# LP_ECG_Power-X02.net
KiCad netlist of a schematic drawn in Altium Designer
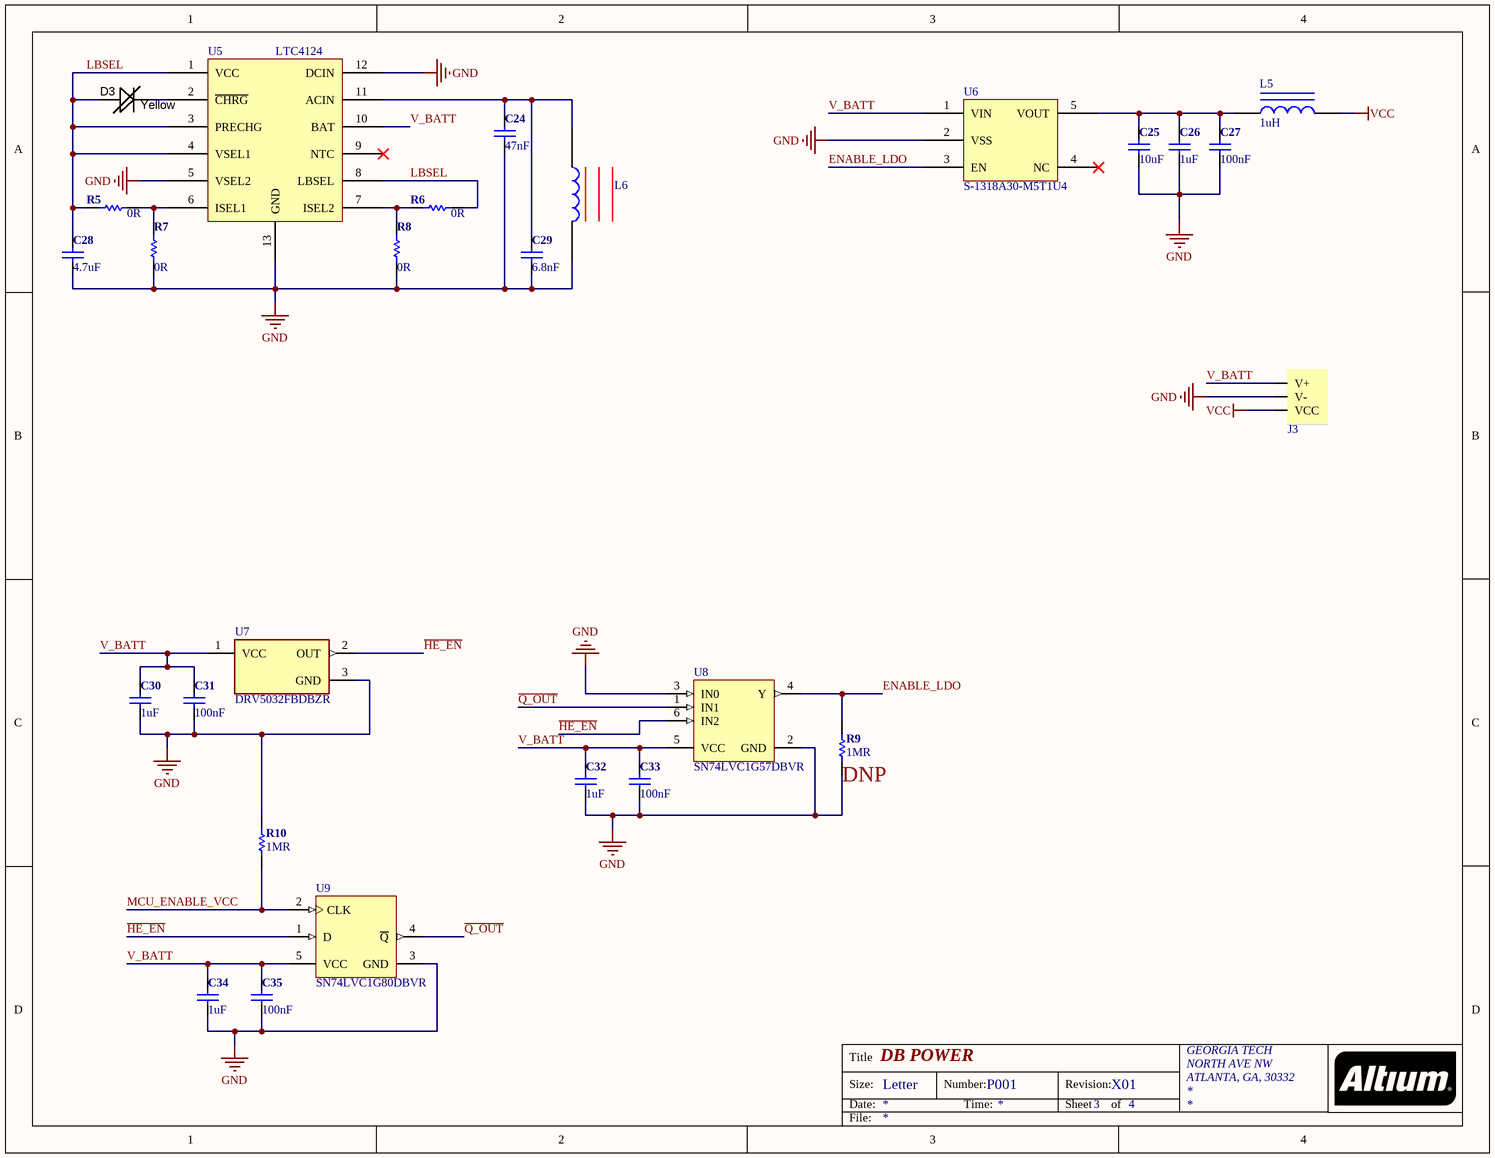
[diagram p0: LP_ECG_Power-X02.SchDoc]

(export (version "E")
  (design (tool "Eeschema 10.0.6"))
  (components
    (comp (ref "C24")
      (value "47nF")
      (footprint "C0402")
      (fields
        (field (name "MANUFACTURER") "Murata")
        (field (name "MANUFACTURER PART NUMBER") "GCM155R71H473KE02D")
      )
      (libsource (lib "LP_ECG-X02") (part "C-0402(1005)"))
    )
    (comp (ref "C25")
      (value "10uF")
      (footprint "C0402")
      (fields
        (field (name "MANUFACTURER") "Kyocera AVX")
        (field (name "MANUFACTURER PART NUMBER") "0402ZD106MAT2A")
      )
      (libsource (lib "LP_ECG-X01") (part "C-0402(1005)"))
    )
    (comp (ref "C26")
      (value "1uF")
      (footprint "C0402")
      (fields
        (field (name "MANUFACTURER") "Yageo")
        (field (name "MANUFACTURER PART NUMBER") "CC0402MRX5R5BB105")
        (field (name "TOLERANCE") "20%")
      )
      (libsource (lib "LP_ECG-X01") (part "C-0402(1005)"))
    )
    (comp (ref "C27")
      (value "100nF")
      (footprint "C0402")
      (fields
        (field (name "MANUFACTURER") "Taiyo Yuden")
        (field (name "MANUFACTURER PART NUMBER") "TMK105BJ104KV-F")
        (field (name "TOLERANCE") "10%")
      )
      (libsource (lib "LP_ECG-X01") (part "C-0402(1005)"))
    )
    (comp (ref "C28")
      (value "4.7uF")
      (footprint "C0402")
      (fields
        (field (name "MANUFACTURER") "Murata")
        (field (name "MANUFACTURER PART NUMBER") "GRM155R60J475ME87J")
      )
      (libsource (lib "LP_ECG-X02") (part "C-0402(1005)"))
    )
    (comp (ref "C29")
      (value "6.8nF")
      (footprint "C0402")
      (fields
        (field (name "MANUFACTURER") "Murata")
        (field (name "MANUFACTURER PART NUMBER") "GCM155R71H682KA55D")
      )
      (libsource (lib "LP_ECG-X02") (part "C-0402(1005)"))
    )
    (comp (ref "C30")
      (value "1uF")
      (footprint "C0402")
      (fields
        (field (name "MANUFACTURER") "Yageo")
        (field (name "MANUFACTURER PART NUMBER") "CC0402MRX5R5BB105")
        (field (name "TOLERANCE") "20%")
      )
      (libsource (lib "LP_ECG-X01") (part "C-0402(1005)"))
    )
    (comp (ref "C31")
      (value "100nF")
      (footprint "C0402")
      (fields
        (field (name "MANUFACTURER") "Taiyo Yuden")
        (field (name "MANUFACTURER PART NUMBER") "TMK105BJ104KV-F")
        (field (name "TOLERANCE") "10%")
      )
      (libsource (lib "LP_ECG-X01") (part "C-0402(1005)"))
    )
    (comp (ref "C32")
      (value "1uF")
      (footprint "C0402")
      (fields
        (field (name "MANUFACTURER") "Yageo")
        (field (name "MANUFACTURER PART NUMBER") "CC0402MRX5R5BB105")
        (field (name "TOLERANCE") "20%")
      )
      (libsource (lib "LP_ECG-X01") (part "C-0402(1005)"))
    )
    (comp (ref "C33")
      (value "100nF")
      (footprint "C0402")
      (fields
        (field (name "MANUFACTURER") "Taiyo Yuden")
        (field (name "MANUFACTURER PART NUMBER") "TMK105BJ104KV-F")
        (field (name "TOLERANCE") "10%")
      )
      (libsource (lib "LP_ECG-X01") (part "C-0402(1005)"))
    )
    (comp (ref "C34")
      (value "1uF")
      (footprint "C0402")
      (fields
        (field (name "MANUFACTURER") "Yageo")
        (field (name "MANUFACTURER PART NUMBER") "CC0402MRX5R5BB105")
        (field (name "TOLERANCE") "20%")
      )
      (libsource (lib "LP_ECG-X01") (part "C-0402(1005)"))
    )
    (comp (ref "C35")
      (value "100nF")
      (footprint "C0402")
      (fields
        (field (name "MANUFACTURER") "Taiyo Yuden")
        (field (name "MANUFACTURER PART NUMBER") "TMK105BJ104KV-F")
        (field (name "TOLERANCE") "10%")
      )
      (libsource (lib "LP_ECG-X01") (part "C-0402(1005)"))
    )
    (comp (ref "D3")
      (value "Yellow")
      (footprint "LED_0402")
      (description "Single Color LED, Super Bright Yellow, Water Clear, 0.8mm")
      (fields
        (field (name "MANUFACTURER") "Kingbright")
        (field (name "MANUFACTURER PART NUMBER") "APHHS1005SYCK")
      )
      (libsource (lib "LP_ECG-X01") (part "LED_0402(1005)"))
    )
    (comp (ref "J3")
      (value "SMD CONNECTOR FOR 40 mAh BATTERY")
      (footprint "battery_connector")
      (description "Lithium Battery 3.7V 40mAh Rechargeable")
      (libsource (lib "LP_ECG-X01") (part "SMD_BATTERY_CONNECTOR"))
    )
    (comp (ref "L5")
      (value "1uH")
      (footprint "L0402")
      (description "General Purpose Inductor, 1uH, 20%, 1 Element, Ferrite-Core, SMD, 0402")
      (fields
        (field (name "MANUFACTURER") "TDK")
        (field (name "MANUFACTURER PART NUMBER") "MLZ1005M1R0WT000")
      )
      (libsource (lib "LP_ECG-X01") (part "Inductor Iron"))
    )
    (comp (ref "L6")
      (value "WIRELESS CHARGING COIL, RECEIVER")
      (footprint "760308101219")
      (description "General Purpose Inductor, 11.8uH, 10%, 1 Element")
      (fields
        (field (name "MANUFACTURER") "Wurth Electronics")
        (field (name "MANUFACTURER PART NUMBER") "760308101219")
      )
      (libsource (lib "LP_ECG-X01") (part "WIRELESS_CHARGING_COIL"))
    )
    (comp (ref "R5")
      (value "0R")
      (footprint "R0402")
      (description "Fixed Resistor, Metal Glaze/thick Film, 0.0625W, 0ohm, Surface Mount, 0402")
      (fields
        (field (name "MANUFACTURER") "Yageo")
        (field (name "MANUFACTURER PART NUMBER") "AC0402JR-070RL")
      )
      (libsource (lib "LP_ECG-X02") (part "R-0402(1005)"))
    )
    (comp (ref "R6")
      (value "0R")
      (footprint "R0402")
      (description "Fixed Resistor, Metal Glaze/thick Film, 0.0625W, 0ohm, Surface Mount, 0402")
      (fields
        (field (name "MANUFACTURER") "Yageo")
        (field (name "MANUFACTURER PART NUMBER") "AC0402JR-070RL")
      )
      (libsource (lib "LP_ECG-X02") (part "R-0402(1005)"))
    )
    (comp (ref "R7")
      (value "0R")
      (footprint "R0402")
      (description "Fixed Resistor, Metal Glaze/thick Film, 0.0625W, 0ohm, Surface Mount, 0402")
      (fields
        (field (name "MANUFACTURER") "Yageo")
        (field (name "MANUFACTURER PART NUMBER") "AC0402JR-070RL")
      )
      (libsource (lib "LP_ECG-X02") (part "R-0402(1005)"))
    )
    (comp (ref "R8")
      (value "0R")
      (footprint "R0402")
      (description "Fixed Resistor, Metal Glaze/thick Film, 0.0625W, 0ohm, Surface Mount, 0402")
      (fields
        (field (name "MANUFACTURER") "Yageo")
        (field (name "MANUFACTURER PART NUMBER") "AC0402JR-070RL")
      )
      (libsource (lib "LP_ECG-X02") (part "R-0402(1005)"))
    )
    (comp (ref "R9")
      (value "1MR")
      (footprint "R0402")
      (fields
        (field (name "MANUFACTURER") "Yageo")
        (field (name "MANUFACTURER PART NUMBER") "AC0402FR-071ML")
        (field (name "TOLERANCE") "1%")
      )
      (libsource (lib "LP_ECG-X01") (part "R-0402(1005)"))
    )
    (comp (ref "R10")
      (value "1MR")
      (footprint "R0402")
      (fields
        (field (name "MANUFACTURER") "Yageo")
        (field (name "MANUFACTURER PART NUMBER") "AC0402FR-071ML")
        (field (name "TOLERANCE") "1%")
      )
      (libsource (lib "LP_ECG-X01") (part "R-0402(1005)"))
    )
    (comp (ref "U5")
      (value "LTC4124")
      (footprint "12-LQFN")
      (description "Power Supply Support Circuit, Adjustable, 1 Channel, CMOS")
      (fields
        (field (name "MANUFACTURER") "Analog Devices")
        (field (name "MANUFACTURER PART NUMBER") "LTC4124EV#TRMPBF")
      )
      (libsource (lib "LP_ECG-X02") (part "LTC4124"))
    )
    (comp (ref "U6")
      (value "S-1318A30-M5T1U4")
      (footprint "SOT-23-5")
      (description "Fixed Positive LDO Regulator")
      (fields (field (name "MANUFACTURER") "ABLIC"))
      (libsource (lib "LP_ECG-X02") (part "S-1318A30-M5T1U4"))
    )
    (comp (ref "U7")
      (value "DRV5032FBDBZR")
      (footprint "FP-DBZ0003A-MFG")
      (description "LP HALL 32FBDBZR")
      (fields (field (name "MANUFACTURER") "Texas Instruments"))
      (libsource (lib "Altium Content Vault") (part "2ac151be60cf6bda0d169f73a696793"))
    )
    (comp (ref "U8")
      (value "SN74LVC1G57DBVR")
      (footprint "DBV0006A_M")
      (description "CONFIGURABLE MULTIPLE-FUNCTION GATE, DBV0006A, LARGE T&R")
      (fields (field (name "MANUFACTURER") "Texas Instruments"))
      (libsource (lib "Altium Content Vault") (part "TI-SN74XXX1GXX-6"))
    )
    (comp (ref "U9")
      (value "SN74LVC1G80DBVR")
      (footprint "DBV0005A_N")
      (description "Single Positive-Edge-Triggered D-Type Flip-Flop, DBV0005A, LARGE T&R")
      (fields (field (name "MANUFACTURER") "Texas Instruments"))
      (libsource (lib "Altium Content Vault") (part "TI-SN74XXX1G80-5"))
    )
  )
  (nets
    (net (code "1") (name "/ENABLE_LDO") (class "Default")
      (node (ref "R9") (pin "1") (pinfunction "1_1") (pintype "passive"))
      (node (ref "U6") (pin "3") (pinfunction "EN_3") (pintype "passive"))
      (node (ref "U8") (pin "4") (pinfunction "Y_4") (pintype "output"))
    )
    (net (code "2") (name "/LBSEL") (class "Default")
      (node (ref "C28") (pin "1") (pinfunction "1_1") (pintype "passive"))
      (node (ref "D3") (pin "A") (pinfunction "A_A") (pintype "passive"))
      (node (ref "R5") (pin "1") (pinfunction "1_1") (pintype "passive"))
      (node (ref "R6") (pin "2") (pinfunction "2_2") (pintype "passive"))
      (node (ref "U5") (pin "1") (pinfunction "VCC_1") (pintype "passive"))
      (node (ref "U5") (pin "3") (pinfunction "PRECHG_3") (pintype "passive"))
      (node (ref "U5") (pin "4") (pinfunction "VSEL1_4") (pintype "passive"))
      (node (ref "U5") (pin "8") (pinfunction "LBSEL_8") (pintype "passive"))
    )
    (net (code "3") (name "/MCU_ENABLE_VCC") (class "Default")
      (node (ref "R10") (pin "2") (pinfunction "2_2") (pintype "passive"))
      (node (ref "U9") (pin "2") (pinfunction "CLK_2") (pintype "input"))
    )
    (net (code "4") (name "/V_BATT") (class "Default")
      (node (ref "C30") (pin "1") (pinfunction "1_1") (pintype "passive"))
      (node (ref "C31") (pin "2") (pinfunction "2_2") (pintype "passive"))
      (node (ref "C32") (pin "1") (pinfunction "1_1") (pintype "passive"))
      (node (ref "C33") (pin "2") (pinfunction "2_2") (pintype "passive"))
      (node (ref "C34") (pin "1") (pinfunction "1_1") (pintype "passive"))
      (node (ref "C35") (pin "2") (pinfunction "2_2") (pintype "passive"))
      (node (ref "J3") (pin "1") (pinfunction "V+_1") (pintype "power_in"))
      (node (ref "U5") (pin "10") (pinfunction "BAT_10") (pintype "passive"))
      (node (ref "U6") (pin "1") (pinfunction "VIN_1") (pintype "passive"))
      (node (ref "U7") (pin "1") (pinfunction "VCC_1") (pintype "power_in"))
      (node (ref "U8") (pin "5") (pinfunction "VCC_5") (pintype "power_in"))
      (node (ref "U9") (pin "5") (pinfunction "VCC_5") (pintype "power_in"))
    )
    (net (code "5") (name "/~{HE_EN}") (class "Default")
      (node (ref "U7") (pin "2") (pinfunction "OUT_2") (pintype "output"))
      (node (ref "U8") (pin "6") (pinfunction "IN2_6") (pintype "input"))
      (node (ref "U9") (pin "1") (pinfunction "D_1") (pintype "input"))
    )
    (net (code "6") (name "/~{Q_OUT}") (class "Default")
      (node (ref "U8") (pin "1") (pinfunction "IN1_1") (pintype "input"))
      (node (ref "U9") (pin "4") (pinfunction "~{Q}_4") (pintype "output"))
    )
    (net (code "7") (name "GND") (class "Default")
      (node (ref "C24") (pin "2") (pinfunction "2_2") (pintype "passive"))
      (node (ref "C25") (pin "2") (pinfunction "2_2") (pintype "passive"))
      (node (ref "C26") (pin "2") (pinfunction "2_2") (pintype "passive"))
      (node (ref "C27") (pin "1") (pinfunction "1_1") (pintype "passive"))
      (node (ref "C28") (pin "2") (pinfunction "2_2") (pintype "passive"))
      (node (ref "C29") (pin "2") (pinfunction "2_2") (pintype "passive"))
      (node (ref "C30") (pin "2") (pinfunction "2_2") (pintype "passive"))
      (node (ref "C31") (pin "1") (pinfunction "1_1") (pintype "passive"))
      (node (ref "C32") (pin "2") (pinfunction "2_2") (pintype "passive"))
      (node (ref "C33") (pin "1") (pinfunction "1_1") (pintype "passive"))
      (node (ref "C34") (pin "2") (pinfunction "2_2") (pintype "passive"))
      (node (ref "C35") (pin "1") (pinfunction "1_1") (pintype "passive"))
      (node (ref "J3") (pin "2") (pinfunction "V-_2") (pintype "power_in"))
      (node (ref "L6") (pin "2") (pinfunction "2_2") (pintype "passive"))
      (node (ref "R10") (pin "1") (pinfunction "1_1") (pintype "passive"))
      (node (ref "R7") (pin "2") (pinfunction "2_2") (pintype "passive"))
      (node (ref "R8") (pin "2") (pinfunction "2_2") (pintype "passive"))
      (node (ref "R9") (pin "2") (pinfunction "2_2") (pintype "passive"))
      (node (ref "U5") (pin "12") (pinfunction "DCIN_12") (pintype "passive"))
      (node (ref "U5") (pin "13") (pinfunction "GND_13") (pintype "passive"))
      (node (ref "U5") (pin "5") (pinfunction "VSEL2_5") (pintype "passive"))
      (node (ref "U6") (pin "2") (pinfunction "VSS_2") (pintype "passive"))
      (node (ref "U7") (pin "3") (pinfunction "GND_3") (pintype "power_in"))
      (node (ref "U8") (pin "2") (pinfunction "GND_2") (pintype "power_in"))
      (node (ref "U8") (pin "3") (pinfunction "IN0_3") (pintype "input"))
      (node (ref "U9") (pin "3") (pinfunction "GND_3") (pintype "power_in"))
    )
    (net (code "8") (name "Net-(U5-ACIN)") (class "Default")
      (node (ref "C24") (pin "1") (pinfunction "1_1") (pintype "passive"))
      (node (ref "C29") (pin "1") (pinfunction "1_1") (pintype "passive"))
      (node (ref "L6") (pin "1") (pinfunction "1_1") (pintype "passive"))
      (node (ref "U5") (pin "11") (pinfunction "ACIN_11") (pintype "passive"))
    )
    (net (code "9") (name "Net-(U5-ISEL1)") (class "Default")
      (node (ref "R5") (pin "2") (pinfunction "2_2") (pintype "passive"))
      (node (ref "R7") (pin "1") (pinfunction "1_1") (pintype "passive"))
      (node (ref "U5") (pin "6") (pinfunction "ISEL1_6") (pintype "passive"))
    )
    (net (code "10") (name "Net-(U5-ISEL2)") (class "Default")
      (node (ref "R6") (pin "1") (pinfunction "1_1") (pintype "passive"))
      (node (ref "R8") (pin "1") (pinfunction "1_1") (pintype "passive"))
      (node (ref "U5") (pin "7") (pinfunction "ISEL2_7") (pintype "passive"))
    )
    (net (code "11") (name "Net-(U5-~{CHRG})") (class "Default")
      (node (ref "D3") (pin "K") (pinfunction "K_K") (pintype "passive"))
      (node (ref "U5") (pin "2") (pinfunction "~{CHRG}_2") (pintype "passive"))
    )
    (net (code "12") (name "Net-(U6-VOUT)") (class "Default")
      (node (ref "C25") (pin "1") (pinfunction "1_1") (pintype "passive"))
      (node (ref "C26") (pin "1") (pinfunction "1_1") (pintype "passive"))
      (node (ref "C27") (pin "2") (pinfunction "2_2") (pintype "passive"))
      (node (ref "L5") (pin "1") (pinfunction "1_1") (pintype "passive"))
      (node (ref "U6") (pin "5") (pinfunction "VOUT_5") (pintype "passive"))
    )
    (net (code "13") (name "VCC") (class "Default")
      (node (ref "J3") (pin "3") (pinfunction "VCC_3") (pintype "power_in"))
      (node (ref "L5") (pin "2") (pinfunction "2_2") (pintype "passive"))
    )
    (net (code "14") (name "unconnected-(U5-NTC-Pad9)") (class "Default")
      (node (ref "U5") (pin "9") (pinfunction "NTC_9") (pintype "passive+no_connect"))
    )
    (net (code "15") (name "unconnected-(U6-NC-Pad4)") (class "Default")
      (node (ref "U6") (pin "4") (pinfunction "NC_4") (pintype "passive+no_connect"))
    )
  )
)
